# Gas_Sensor_PCB.net
KiCad netlist of a schematic drawn in EAGLE
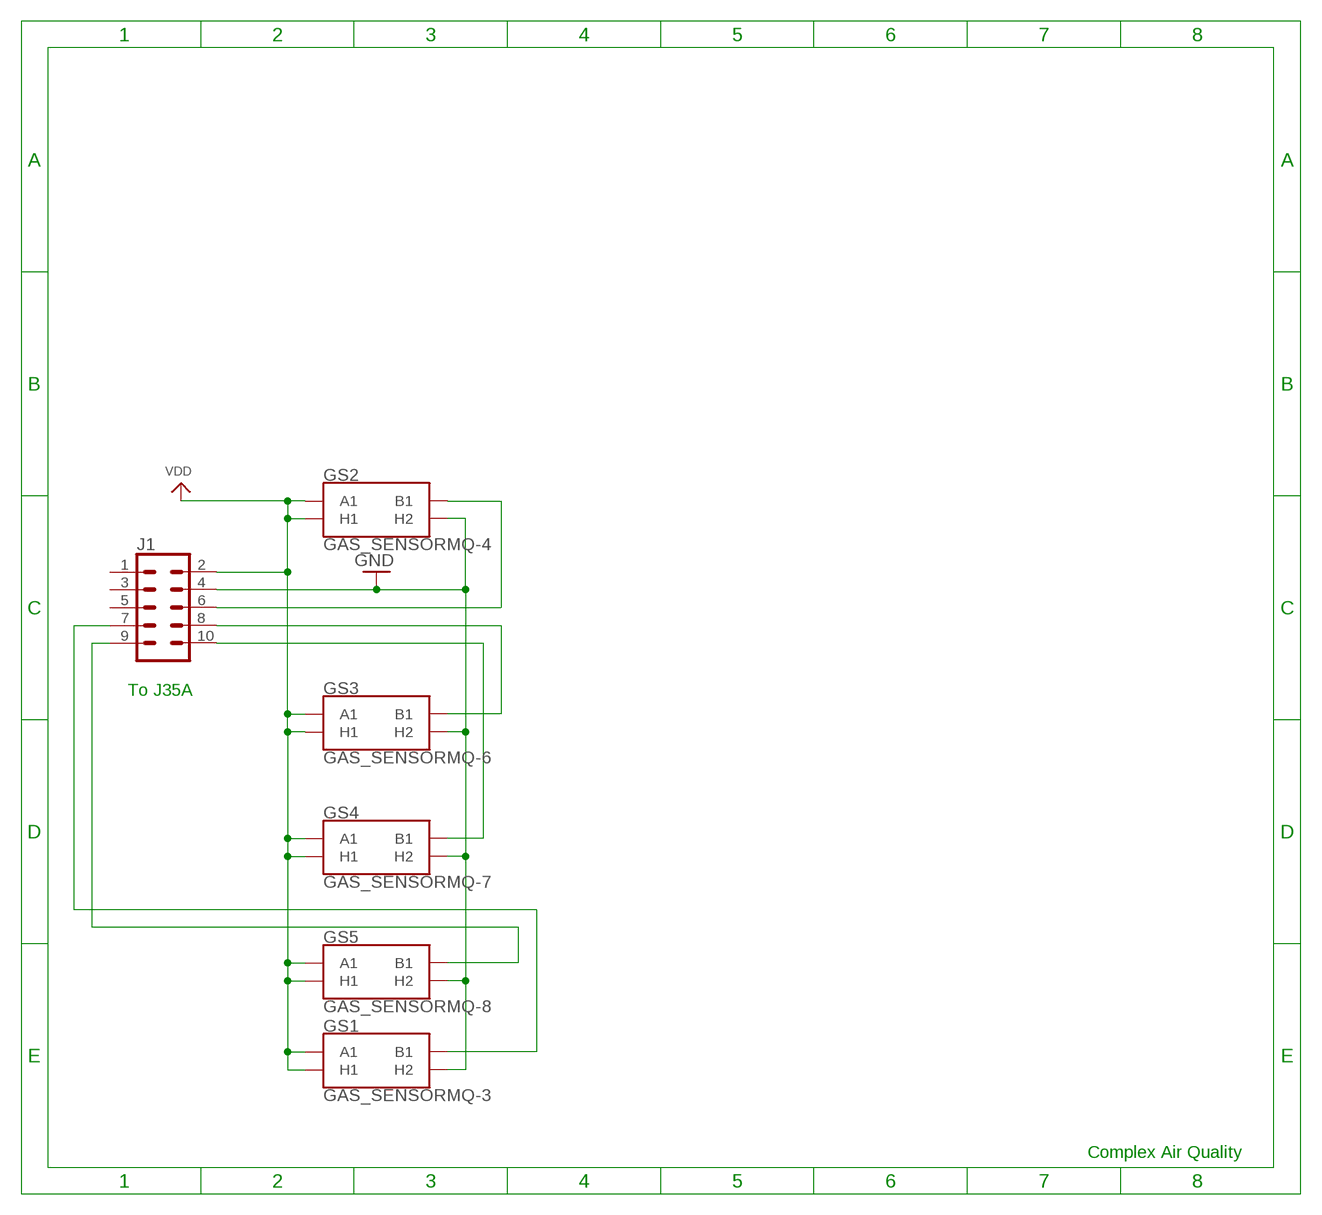
[diagram p0: schematic, sheet 1]

(export (version "E")
  (design (tool "Eeschema 10.0.6"))
  (components
    (comp (ref "GS1")
      (value "GAS_SENSORMQ-3")
      (footprint "eagle-import:GAS_SENSOR")
      (libsource (lib "eagle-import") (part "GAS_SENSORMQ-3"))
    )
    (comp (ref "GS2")
      (value "GAS_SENSORMQ-4")
      (footprint "eagle-import:GAS_SENSOR")
      (libsource (lib "eagle-import") (part "GAS_SENSORMQ-4"))
    )
    (comp (ref "GS3")
      (value "GAS_SENSORMQ-6")
      (footprint "eagle-import:GAS_SENSOR")
      (libsource (lib "eagle-import") (part "GAS_SENSORMQ-6"))
    )
    (comp (ref "GS4")
      (value "GAS_SENSORMQ-7")
      (footprint "eagle-import:GAS_SENSOR")
      (libsource (lib "eagle-import") (part "GAS_SENSORMQ-7"))
    )
    (comp (ref "GS5")
      (value "GAS_SENSORMQ-8")
      (footprint "eagle-import:GAS_SENSOR")
      (libsource (lib "eagle-import") (part "GAS_SENSORMQ-8"))
    )
    (comp (ref "J1")
      (value "CONN_05X2SHD")
      (footprint "eagle-import:2X5-SHROUDED")
      (libsource (lib "eagle-import") (part "CONN_05X2SHD"))
    )
  )
  (nets
    (net (code "1") (name "GND") (class "Default")
      (node (ref "GS1") (pin "HB") (pinfunction "H2_HB") (pintype "bidirectional"))
      (node (ref "GS2") (pin "HB") (pinfunction "H2_HB") (pintype "bidirectional"))
      (node (ref "GS3") (pin "HB") (pinfunction "H2_HB") (pintype "bidirectional"))
      (node (ref "GS4") (pin "HB") (pinfunction "H2_HB") (pintype "bidirectional"))
      (node (ref "GS5") (pin "HB") (pinfunction "H2_HB") (pintype "bidirectional"))
      (node (ref "J1") (pin "4") (pinfunction "4_4") (pintype "passive"))
    )
    (net (code "2") (name "Net-(GS1-PadB1)") (class "Default")
      (node (ref "GS1") (pin "B1") (pinfunction "B1_B1") (pintype "bidirectional"))
      (node (ref "J1") (pin "7") (pinfunction "7_7") (pintype "passive"))
    )
    (net (code "3") (name "Net-(GS2-PadB1)") (class "Default")
      (node (ref "GS2") (pin "B1") (pinfunction "B1_B1") (pintype "bidirectional"))
      (node (ref "J1") (pin "6") (pinfunction "6_6") (pintype "passive"))
    )
    (net (code "4") (name "Net-(GS3-PadB1)") (class "Default")
      (node (ref "GS3") (pin "B1") (pinfunction "B1_B1") (pintype "bidirectional"))
      (node (ref "J1") (pin "8") (pinfunction "8_8") (pintype "passive"))
    )
    (net (code "5") (name "Net-(GS4-PadB1)") (class "Default")
      (node (ref "GS4") (pin "B1") (pinfunction "B1_B1") (pintype "bidirectional"))
      (node (ref "J1") (pin "10") (pinfunction "10_10") (pintype "passive"))
    )
    (net (code "6") (name "Net-(GS5-PadB1)") (class "Default")
      (node (ref "GS5") (pin "B1") (pinfunction "B1_B1") (pintype "bidirectional"))
      (node (ref "J1") (pin "9") (pinfunction "9_9") (pintype "passive"))
    )
    (net (code "7") (name "VDD") (class "Default")
      (node (ref "GS1") (pin "A1") (pinfunction "A1_A1") (pintype "bidirectional"))
      (node (ref "GS1") (pin "HA") (pinfunction "H1_HA") (pintype "bidirectional"))
      (node (ref "GS2") (pin "A1") (pinfunction "A1_A1") (pintype "bidirectional"))
      (node (ref "GS2") (pin "HA") (pinfunction "H1_HA") (pintype "bidirectional"))
      (node (ref "GS3") (pin "A1") (pinfunction "A1_A1") (pintype "bidirectional"))
      (node (ref "GS3") (pin "HA") (pinfunction "H1_HA") (pintype "bidirectional"))
      (node (ref "GS4") (pin "A1") (pinfunction "A1_A1") (pintype "bidirectional"))
      (node (ref "GS4") (pin "HA") (pinfunction "H1_HA") (pintype "bidirectional"))
      (node (ref "GS5") (pin "A1") (pinfunction "A1_A1") (pintype "bidirectional"))
      (node (ref "GS5") (pin "HA") (pinfunction "H1_HA") (pintype "bidirectional"))
      (node (ref "J1") (pin "2") (pinfunction "2_2") (pintype "passive"))
    )
    (net (code "8") (name "unconnected-(J1-Pad1)") (class "Default")
      (node (ref "J1") (pin "1") (pinfunction "1_1") (pintype "passive"))
    )
    (net (code "9") (name "unconnected-(J1-Pad3)") (class "Default")
      (node (ref "J1") (pin "3") (pinfunction "3_3") (pintype "passive"))
    )
    (net (code "10") (name "unconnected-(J1-Pad5)") (class "Default")
      (node (ref "J1") (pin "5") (pinfunction "5_5") (pintype "passive"))
    )
  )
)
